# DHT22_schematic.net
KiCad netlist of a schematic drawn in EAGLE
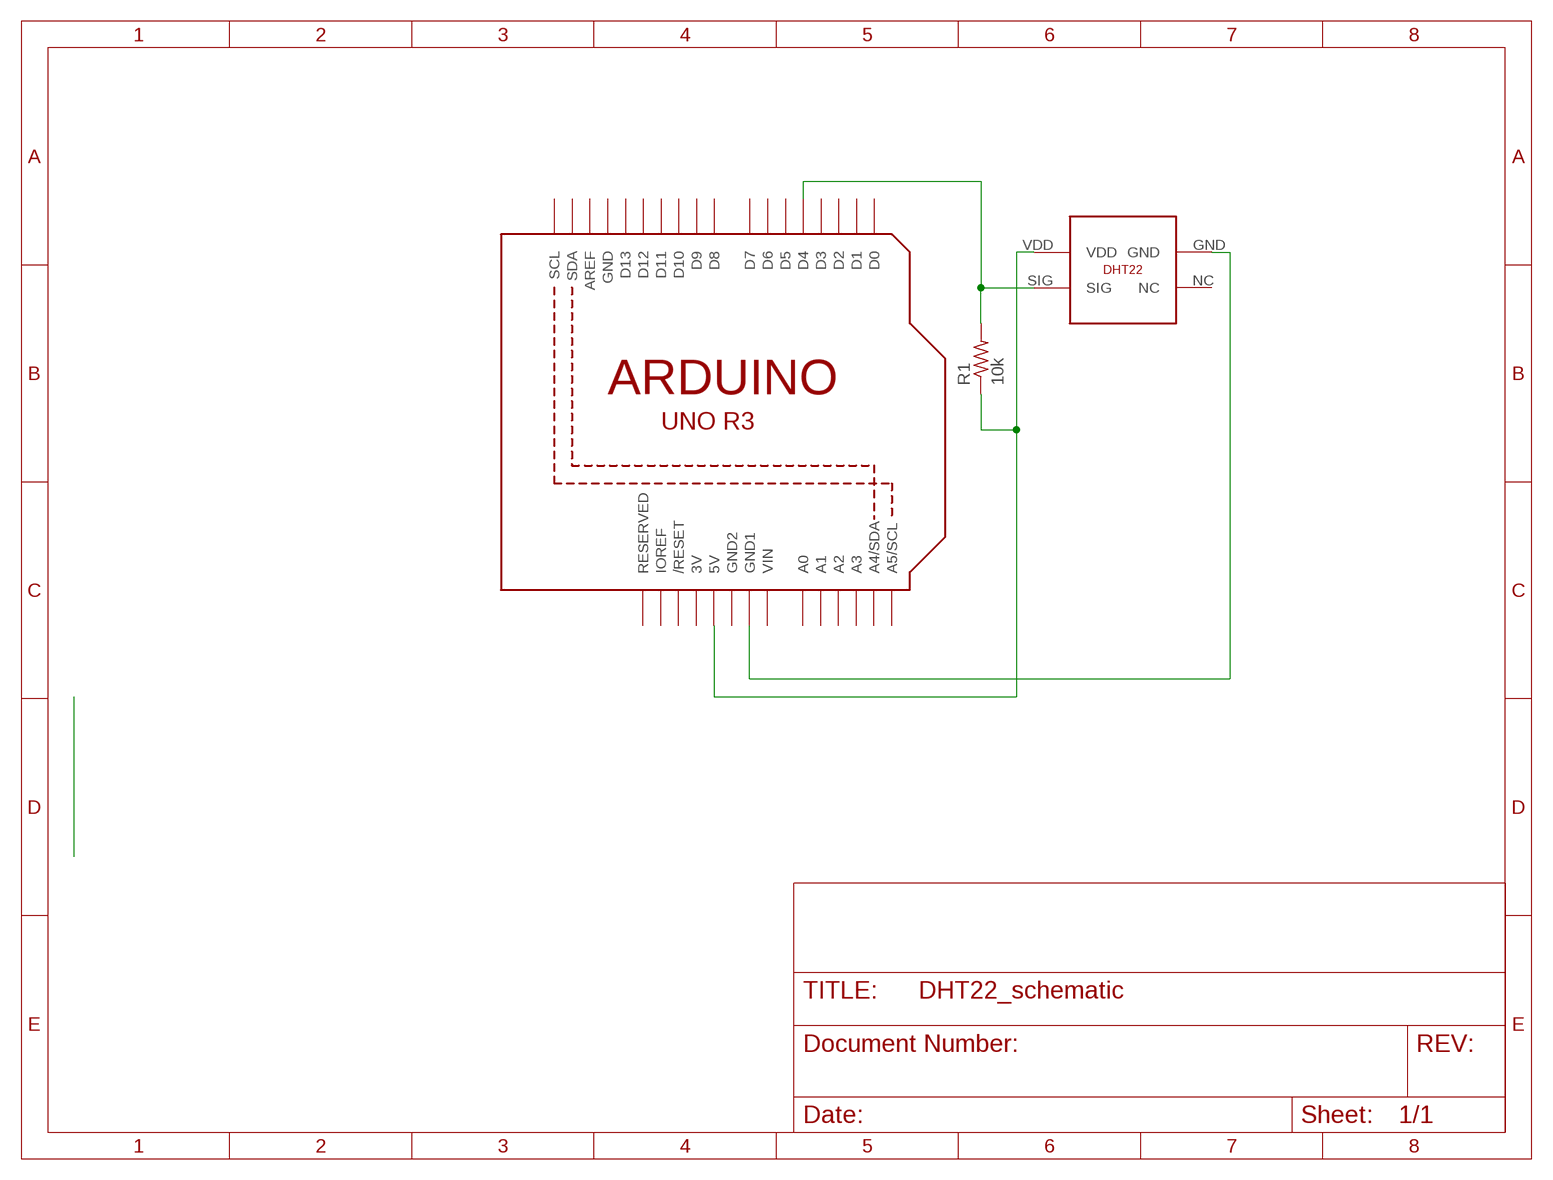
[diagram p0: schematic, sheet 1]

(export (version "E")
  (design (tool "Eeschema 10.0.6"))
  (components
    (comp (ref "R1")
      (value "10k")
      (footprint "eagle-import:R0402")
      (libsource (lib "eagle-import") (part "R-US_R0402"))
    )
    (comp (ref "U$3")
      (value "DHT22")
      (footprint "eagle-import:DHT22_HEADERS")
      (libsource (lib "eagle-import") (part "DHT22"))
    )
    (comp (ref "U1")
      (value "ARDUINOR3-DIMENSION")
      (footprint "eagle-import:ARDUINOR3")
      (libsource (lib "eagle-import") (part "ARDUINOR3-DIMENSION"))
    )
  )
  (nets
    (net (code "1") (name "/3V") (class "Default")
      (node (ref "U1") (pin "3V") (pinfunction "3V_3V") (pintype "power_in"))
    )
    (net (code "2") (name "/GND") (class "Default")
      (node (ref "U1") (pin "GND") (pinfunction "GND_GND") (pintype "power_in"))
    )
    (net (code "3") (name "/GND2") (class "Default")
      (node (ref "U1") (pin "GND2") (pinfunction "GND2_GND2") (pintype "power_in"))
    )
    (net (code "4") (name "/VIN") (class "Default")
      (node (ref "U1") (pin "VIN") (pinfunction "VIN_VIN") (pintype "power_in"))
    )
    (net (code "5") (name "Net-(R1-Pad1)") (class "Default")
      (node (ref "R1") (pin "1") (pinfunction "1_1") (pintype "passive"))
      (node (ref "U$3") (pin "VDD") (pinfunction "VDD_VDD") (pintype "power_in"))
      (node (ref "U1") (pin "5V") (pinfunction "5V_5V") (pintype "power_in"))
    )
    (net (code "6") (name "Net-(R1-Pad2)") (class "Default")
      (node (ref "R1") (pin "2") (pinfunction "2_2") (pintype "passive"))
      (node (ref "U$3") (pin "SIG") (pinfunction "SIG_SIG") (pintype "bidirectional"))
      (node (ref "U1") (pin "D4") (pinfunction "D4_D4") (pintype "bidirectional"))
    )
    (net (code "7") (name "Net-(U$3-PadGND)") (class "Default")
      (node (ref "U$3") (pin "GND") (pinfunction "GND_GND") (pintype "power_in"))
      (node (ref "U1") (pin "GND1") (pinfunction "GND1_GND1") (pintype "power_in"))
    )
    (net (code "8") (name "unconnected-(U$3-PadNC)") (class "Default")
      (node (ref "U$3") (pin "NC") (pinfunction "NC_NC") (pintype "no_connect"))
    )
    (net (code "9") (name "unconnected-(U1-A4{slash}SDA-PadA4)") (class "Default")
      (node (ref "U1") (pin "A4") (pinfunction "A4/SDA_A4") (pintype "bidirectional"))
    )
    (net (code "10") (name "unconnected-(U1-A5{slash}SCL-PadA5)") (class "Default")
      (node (ref "U1") (pin "A5") (pinfunction "A5/SCL_A5") (pintype "bidirectional"))
    )
    (net (code "11") (name "unconnected-(U1-PadA0)") (class "Default")
      (node (ref "U1") (pin "A0") (pinfunction "A0_A0") (pintype "bidirectional"))
    )
    (net (code "12") (name "unconnected-(U1-PadA1)") (class "Default")
      (node (ref "U1") (pin "A1") (pinfunction "A1_A1") (pintype "bidirectional"))
    )
    (net (code "13") (name "unconnected-(U1-PadA2)") (class "Default")
      (node (ref "U1") (pin "A2") (pinfunction "A2_A2") (pintype "bidirectional"))
    )
    (net (code "14") (name "unconnected-(U1-PadA3)") (class "Default")
      (node (ref "U1") (pin "A3") (pinfunction "A3_A3") (pintype "bidirectional"))
    )
    (net (code "15") (name "unconnected-(U1-PadAREF)") (class "Default")
      (node (ref "U1") (pin "AREF") (pinfunction "AREF_AREF") (pintype "bidirectional"))
    )
    (net (code "16") (name "unconnected-(U1-PadD0)") (class "Default")
      (node (ref "U1") (pin "D0") (pinfunction "D0_D0") (pintype "bidirectional"))
    )
    (net (code "17") (name "unconnected-(U1-PadD1)") (class "Default")
      (node (ref "U1") (pin "D1") (pinfunction "D1_D1") (pintype "bidirectional"))
    )
    (net (code "18") (name "unconnected-(U1-PadD2)") (class "Default")
      (node (ref "U1") (pin "D2") (pinfunction "D2_D2") (pintype "bidirectional"))
    )
    (net (code "19") (name "unconnected-(U1-PadD3)") (class "Default")
      (node (ref "U1") (pin "D3") (pinfunction "D3_D3") (pintype "bidirectional"))
    )
    (net (code "20") (name "unconnected-(U1-PadD5)") (class "Default")
      (node (ref "U1") (pin "D5") (pinfunction "D5_D5") (pintype "bidirectional"))
    )
    (net (code "21") (name "unconnected-(U1-PadD6)") (class "Default")
      (node (ref "U1") (pin "D6") (pinfunction "D6_D6") (pintype "bidirectional"))
    )
    (net (code "22") (name "unconnected-(U1-PadD7)") (class "Default")
      (node (ref "U1") (pin "D7") (pinfunction "D7_D7") (pintype "bidirectional"))
    )
    (net (code "23") (name "unconnected-(U1-PadD8)") (class "Default")
      (node (ref "U1") (pin "D8") (pinfunction "D8_D8") (pintype "bidirectional"))
    )
    (net (code "24") (name "unconnected-(U1-PadD9)") (class "Default")
      (node (ref "U1") (pin "D9") (pinfunction "D9_D9") (pintype "bidirectional"))
    )
    (net (code "25") (name "unconnected-(U1-PadD10)") (class "Default")
      (node (ref "U1") (pin "D10") (pinfunction "D10_D10") (pintype "bidirectional"))
    )
    (net (code "26") (name "unconnected-(U1-PadD11)") (class "Default")
      (node (ref "U1") (pin "D11") (pinfunction "D11_D11") (pintype "bidirectional"))
    )
    (net (code "27") (name "unconnected-(U1-PadD12)") (class "Default")
      (node (ref "U1") (pin "D12") (pinfunction "D12_D12") (pintype "bidirectional"))
    )
    (net (code "28") (name "unconnected-(U1-PadD13)") (class "Default")
      (node (ref "U1") (pin "D13") (pinfunction "D13_D13") (pintype "bidirectional"))
    )
    (net (code "29") (name "unconnected-(U1-PadIOREF)") (class "Default")
      (node (ref "U1") (pin "IOREF") (pinfunction "IOREF_IOREF") (pintype "output"))
    )
    (net (code "30") (name "unconnected-(U1-PadRESERVED)") (class "Default")
      (node (ref "U1") (pin "RESERVED") (pinfunction "RESERVED_RESERVED") (pintype "no_connect"))
    )
    (net (code "31") (name "unconnected-(U1-PadSCL)") (class "Default")
      (node (ref "U1") (pin "SCL") (pinfunction "SCL_SCL") (pintype "bidirectional"))
    )
    (net (code "32") (name "unconnected-(U1-PadSDA)") (class "Default")
      (node (ref "U1") (pin "SDA") (pinfunction "SDA_SDA") (pintype "bidirectional"))
    )
    (net (code "33") (name "unconnected-(U1-{slash}RESET-PadRESET)") (class "Default")
      (node (ref "U1") (pin "RESET") (pinfunction "/RESET_RESET") (pintype "bidirectional"))
    )
  )
)
